# Expand_v1_01.net
KiCad netlist of a schematic drawn in EAGLE
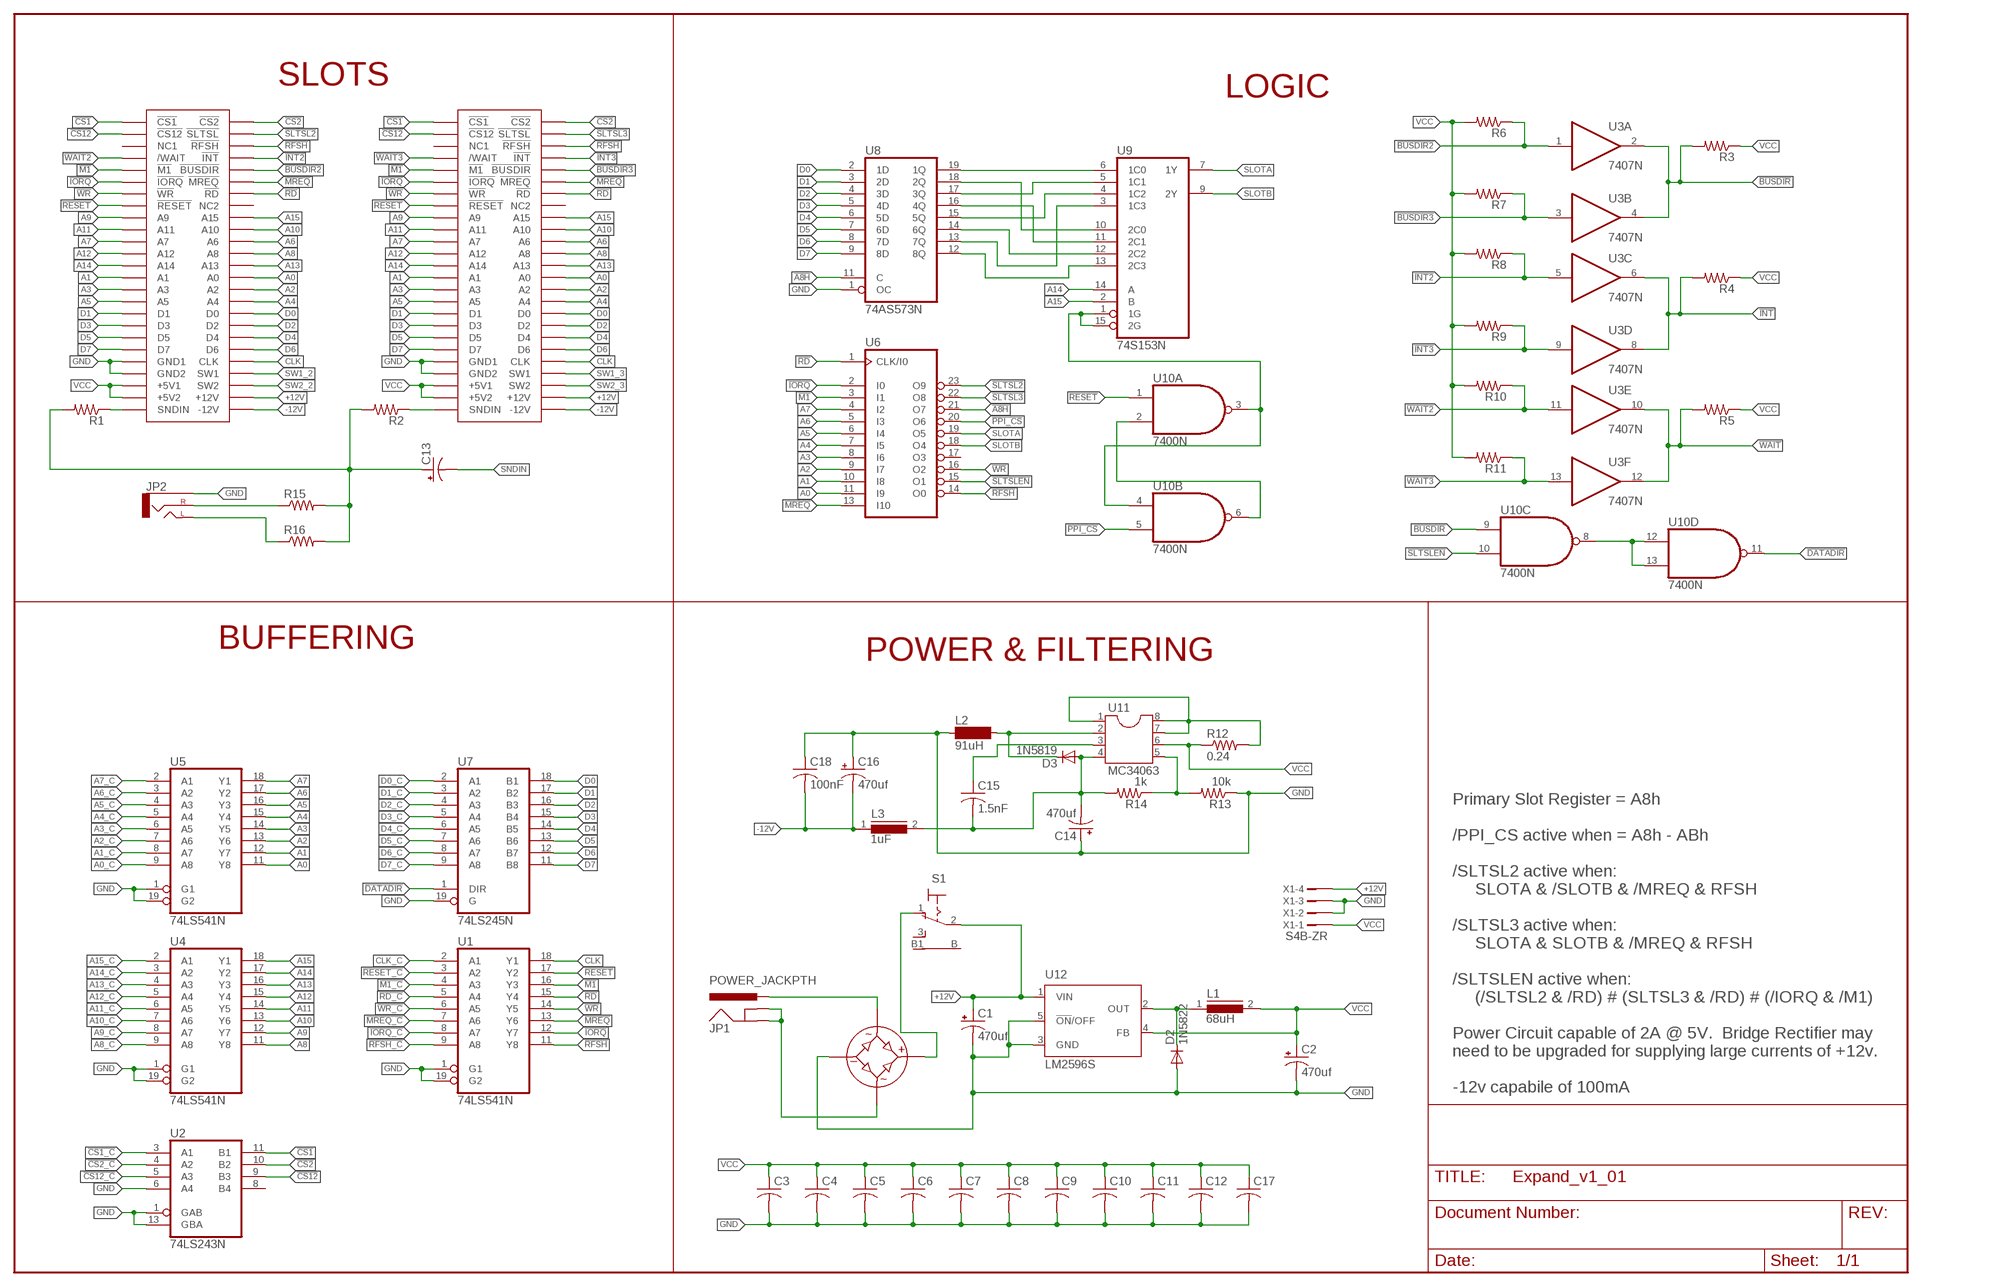
[diagram p0: schematic, sheet 1]

(export (version "E")
  (design (tool "Eeschema 10.0.6"))
  (components
    (comp (ref "C1")
      (value "470uf")
      (footprint "eagle-import:E5-10,5")
      (libsource (lib "eagle-import") (part "CPOL-USE5-10.5"))
    )
    (comp (ref "C2")
      (value "470uf")
      (footprint "eagle-import:E5-10,5")
      (libsource (lib "eagle-import") (part "CPOL-USE5-10.5"))
    )
    (comp (ref "C3")
      (value "C-US050-030X075")
      (footprint "eagle-import:C050-030X075")
      (libsource (lib "eagle-import") (part "C-US050-030X075"))
    )
    (comp (ref "C4")
      (value "C-US050-030X075")
      (footprint "eagle-import:C050-030X075")
      (libsource (lib "eagle-import") (part "C-US050-030X075"))
    )
    (comp (ref "C5")
      (value "C-US050-030X075")
      (footprint "eagle-import:C050-030X075")
      (libsource (lib "eagle-import") (part "C-US050-030X075"))
    )
    (comp (ref "C6")
      (value "C-US050-030X075")
      (footprint "eagle-import:C050-030X075")
      (libsource (lib "eagle-import") (part "C-US050-030X075"))
    )
    (comp (ref "C7")
      (value "C-US050-030X075")
      (footprint "eagle-import:C050-030X075")
      (libsource (lib "eagle-import") (part "C-US050-030X075"))
    )
    (comp (ref "C8")
      (value "C-US050-030X075")
      (footprint "eagle-import:C050-030X075")
      (libsource (lib "eagle-import") (part "C-US050-030X075"))
    )
    (comp (ref "C9")
      (value "C-US050-030X075")
      (footprint "eagle-import:C050-030X075")
      (libsource (lib "eagle-import") (part "C-US050-030X075"))
    )
    (comp (ref "C10")
      (value "C-US050-030X075")
      (footprint "eagle-import:C050-030X075")
      (libsource (lib "eagle-import") (part "C-US050-030X075"))
    )
    (comp (ref "C11")
      (value "C-US050-030X075")
      (footprint "eagle-import:C050-030X075")
      (libsource (lib "eagle-import") (part "C-US050-030X075"))
    )
    (comp (ref "C12")
      (value "C-US050-030X075")
      (footprint "eagle-import:C050-030X075")
      (libsource (lib "eagle-import") (part "C-US050-030X075"))
    )
    (comp (ref "C13")
      (value "CPOL-USE2-4")
      (footprint "eagle-import:E2-4")
      (libsource (lib "eagle-import") (part "CPOL-USE2-4"))
    )
    (comp (ref "C14")
      (value "470uf")
      (footprint "eagle-import:E5-10,5")
      (libsource (lib "eagle-import") (part "CPOL-USE5-10.5"))
    )
    (comp (ref "C15")
      (value "1.5nF")
      (footprint "eagle-import:C050-030X075")
      (libsource (lib "eagle-import") (part "C-US050-030X075"))
    )
    (comp (ref "C16")
      (value "470uf")
      (footprint "eagle-import:E5-10,5")
      (libsource (lib "eagle-import") (part "CPOL-USE5-10.5"))
    )
    (comp (ref "C17")
      (value "C-US050-030X075")
      (footprint "eagle-import:C050-030X075")
      (libsource (lib "eagle-import") (part "C-US050-030X075"))
    )
    (comp (ref "C18")
      (value "100nF")
      (footprint "eagle-import:C050-030X075")
      (libsource (lib "eagle-import") (part "C-US050-030X075"))
    )
    (comp (ref "D1")
      (value "2W10")
      (footprint "eagle-import:2W10")
      (libsource (lib "eagle-import") (part "2W10"))
    )
    (comp (ref "D2")
      (value "1N5822")
      (footprint "eagle-import:DO201-15")
      (libsource (lib "eagle-import") (part "1N5624"))
    )
    (comp (ref "D3")
      (value "1N5819")
      (footprint "eagle-import:DO15-12")
      (libsource (lib "eagle-import") (part "DIODE-DO15-12"))
    )
    (comp (ref "JP1")
      (value "POWER_JACKPTH")
      (footprint "eagle-import:POWER_JACK_PTH")
      (libsource (lib "eagle-import") (part "POWER_JACKPTH"))
    )
    (comp (ref "JP2")
      (value "AUDIO-JACK1:1")
      (footprint "eagle-import:STEREOJACK2.5MM")
      (libsource (lib "eagle-import") (part "AUDIO-JACK1{colon}1"))
    )
    (comp (ref "L1")
      (value "68uH")
      (footprint "eagle-import:A26GFC")
      (libsource (lib "eagle-import") (part "A26GFC"))
    )
    (comp (ref "L2")
      (value "91uH")
      (footprint "eagle-import:BS11")
      (libsource (lib "eagle-import") (part "BS11"))
    )
    (comp (ref "L3")
      (value "1uF")
      (footprint "eagle-import:MCC10")
      (libsource (lib "eagle-import") (part "MCC10"))
    )
    (comp (ref "R1")
      (value "R-US_0207/7")
      (footprint "eagle-import:0207_7")
      (libsource (lib "eagle-import") (part "R-US_0207/7"))
    )
    (comp (ref "R2")
      (value "R-US_0207/7")
      (footprint "eagle-import:0207_7")
      (libsource (lib "eagle-import") (part "R-US_0207/7"))
    )
    (comp (ref "R3")
      (value "R-US_0207/7")
      (footprint "eagle-import:0207_7")
      (libsource (lib "eagle-import") (part "R-US_0207/7"))
    )
    (comp (ref "R4")
      (value "R-US_0207/7")
      (footprint "eagle-import:0207_7")
      (libsource (lib "eagle-import") (part "R-US_0207/7"))
    )
    (comp (ref "R5")
      (value "R-US_0207/7")
      (footprint "eagle-import:0207_7")
      (libsource (lib "eagle-import") (part "R-US_0207/7"))
    )
    (comp (ref "R6")
      (value "R-US_0207/7")
      (footprint "eagle-import:0207_7")
      (libsource (lib "eagle-import") (part "R-US_0207/7"))
    )
    (comp (ref "R7")
      (value "R-US_0207/7")
      (footprint "eagle-import:0207_7")
      (libsource (lib "eagle-import") (part "R-US_0207/7"))
    )
    (comp (ref "R8")
      (value "R-US_0207/7")
      (footprint "eagle-import:0207_7")
      (libsource (lib "eagle-import") (part "R-US_0207/7"))
    )
    (comp (ref "R9")
      (value "R-US_0207/7")
      (footprint "eagle-import:0207_7")
      (libsource (lib "eagle-import") (part "R-US_0207/7"))
    )
    (comp (ref "R10")
      (value "R-US_0207/7")
      (footprint "eagle-import:0207_7")
      (libsource (lib "eagle-import") (part "R-US_0207/7"))
    )
    (comp (ref "R11")
      (value "R-US_0207/7")
      (footprint "eagle-import:0207_7")
      (libsource (lib "eagle-import") (part "R-US_0207/7"))
    )
    (comp (ref "R12")
      (value "0.24")
      (footprint "eagle-import:0207_7")
      (libsource (lib "eagle-import") (part "R-US_0207/7"))
    )
    (comp (ref "R13")
      (value "10k")
      (footprint "eagle-import:0207_7")
      (libsource (lib "eagle-import") (part "R-US_0207/7"))
    )
    (comp (ref "R14")
      (value "1k")
      (footprint "eagle-import:0207_7")
      (libsource (lib "eagle-import") (part "R-US_0207/7"))
    )
    (comp (ref "R15")
      (value "R-US_0207/7")
      (footprint "eagle-import:0207_7")
      (libsource (lib "eagle-import") (part "R-US_0207/7"))
    )
    (comp (ref "R16")
      (value "R-US_0207/7")
      (footprint "eagle-import:0207_7")
      (libsource (lib "eagle-import") (part "R-US_0207/7"))
    )
    (comp (ref "S1")
      (value "9070-1W")
      (footprint "eagle-import:9070-1W")
      (libsource (lib "eagle-import") (part "9070-1W"))
    )
    (comp (ref "U$1")
      (value "MSX_CART_SLOT")
      (footprint "eagle-import:CART_SLOT")
      (libsource (lib "eagle-import") (part "MSX_CART_SLOT"))
    )
    (comp (ref "U$2")
      (value "MSX_CART_SLOT")
      (footprint "eagle-import:CART_SLOT")
      (libsource (lib "eagle-import") (part "MSX_CART_SLOT"))
    )
    (comp (ref "U1")
      (value "74LS541N")
      (footprint "eagle-import:DIL20")
      (libsource (lib "eagle-import") (part "74541NLS"))
    )
    (comp (ref "U2")
      (value "74LS243N")
      (footprint "eagle-import:DIL14")
      (libsource (lib "eagle-import") (part "74243NLS"))
    )
    (comp (ref "U3")
      (value "7407N")
      (footprint "eagle-import:DIL14")
      (libsource (lib "eagle-import") (part "7407N"))
    )
    (comp (ref "U4")
      (value "74LS541N")
      (footprint "eagle-import:DIL20")
      (libsource (lib "eagle-import") (part "74541NLS"))
    )
    (comp (ref "U5")
      (value "74LS541N")
      (footprint "eagle-import:DIL20")
      (libsource (lib "eagle-import") (part "74541NLS"))
    )
    (comp (ref "U6")
      (value "22V10")
      (footprint "eagle-import:DIL24-3")
      (fields (field (name "MPN") "GAL22V10D-7LPN"))
      (libsource (lib "eagle-import") (part "22V10"))
    )
    (comp (ref "U7")
      (value "74LS245N")
      (footprint "eagle-import:DIL20")
      (libsource (lib "eagle-import") (part "74245NLS"))
    )
    (comp (ref "U8")
      (value "74AS573N")
      (footprint "eagle-import:DIL20")
      (libsource (lib "eagle-import") (part "74573NAS"))
    )
    (comp (ref "U9")
      (value "74S153N")
      (footprint "eagle-import:DIL16")
      (libsource (lib "eagle-import") (part "74153NS"))
    )
    (comp (ref "U10")
      (value "7400N")
      (footprint "eagle-import:DIL14")
      (libsource (lib "eagle-import") (part "7400N"))
    )
    (comp (ref "U11")
      (value "MC34063")
      (footprint "eagle-import:DIL08")
      (libsource (lib "eagle-import") (part "DIL8"))
    )
    (comp (ref "U12")
      (value "LM2596S")
      (footprint "eagle-import:TO263-5")
      (fields (field (name "MF") "NATIONAL SEMICONDUCTOR") (field (name "MPN") "LM2596S-ADJ/NOPB"))
      (libsource (lib "eagle-import") (part "LM2596S"))
    )
    (comp (ref "X1")
      (value "S4B-ZR")
      (footprint "eagle-import:S4B-ZR")
      (fields (field (name "MF") "FARNELL") (field (name "MPN") "S4B-ZR(LF)(SN)"))
      (libsource (lib "eagle-import") (part "?4B-ZRS"))
    )
  )
  (nets
    (net (code "1") (name "+12V") (class "Default")
      (node (ref "C1") (pin "+") (pinfunction "+_+") (pintype "passive"))
      (node (ref "S1") (pin "2") (pinfunction "P_2") (pintype "passive"))
      (node (ref "U$1") (pin "P$48") (pinfunction "+12V_P$48") (pintype "bidirectional"))
      (node (ref "U$2") (pin "P$48") (pinfunction "+12V_P$48") (pintype "bidirectional"))
      (node (ref "U12") (pin "1") (pinfunction "VIN_1") (pintype "input"))
      (node (ref "X1") (pin "4") (pinfunction "1_4") (pintype "passive"))
    )
    (net (code "2") (name "-12V") (class "Default")
      (node (ref "C16") (pin "-") (pinfunction "-_-") (pintype "passive"))
      (node (ref "C18") (pin "2") (pinfunction "2_2") (pintype "passive"))
      (node (ref "L3") (pin "1") (pinfunction "1_1") (pintype "passive"))
      (node (ref "U$1") (pin "P$50") (pinfunction "-12V_P$50") (pintype "bidirectional"))
      (node (ref "U$2") (pin "P$50") (pinfunction "-12V_P$50") (pintype "bidirectional"))
    )
    (net (code "3") (name "/~{A8H}") (class "Default")
      (node (ref "U6") (pin "21") (pinfunction "O7_21") (pintype "bidirectional"))
      (node (ref "U8") (pin "11") (pinfunction "C_11") (pintype "input"))
    )
    (net (code "4") (name "/~{BUSDIR2}") (class "Default")
      (node (ref "R6") (pin "1") (pinfunction "1_1") (pintype "passive"))
      (node (ref "U$1") (pin "P$10") (pinfunction "~{BUSDIR}_P$10") (pintype "bidirectional"))
      (node (ref "U3") (pin "1") (pinfunction "I_1") (pintype "input"))
    )
    (net (code "5") (name "/~{BUSDIR3}") (class "Default")
      (node (ref "R7") (pin "1") (pinfunction "1_1") (pintype "passive"))
      (node (ref "U$2") (pin "P$10") (pinfunction "~{BUSDIR}_P$10") (pintype "bidirectional"))
      (node (ref "U3") (pin "3") (pinfunction "I_3") (pintype "input"))
    )
    (net (code "6") (name "/~{BUSDIR}") (class "Default")
      (node (ref "R3") (pin "2") (pinfunction "2_2") (pintype "passive"))
      (node (ref "U10") (pin "9") (pinfunction "I0_9") (pintype "input"))
      (node (ref "U3") (pin "2") (pinfunction "O_2") (pintype "open_collector"))
      (node (ref "U3") (pin "4") (pinfunction "O_4") (pintype "open_collector"))
    )
    (net (code "7") (name "/~{CS1_C}") (class "Default")
      (node (ref "U2") (pin "3") (pinfunction "A1_3") (pintype "bidirectional"))
    )
    (net (code "8") (name "/~{CS1}") (class "Default")
      (node (ref "U$1") (pin "P$1") (pinfunction "~{CS1}_P$1") (pintype "bidirectional"))
      (node (ref "U$2") (pin "P$1") (pinfunction "~{CS1}_P$1") (pintype "bidirectional"))
      (node (ref "U2") (pin "11") (pinfunction "B1_11") (pintype "bidirectional"))
    )
    (net (code "9") (name "/~{CS2_C}") (class "Default")
      (node (ref "U2") (pin "4") (pinfunction "A2_4") (pintype "bidirectional"))
    )
    (net (code "10") (name "/~{CS2}") (class "Default")
      (node (ref "U$1") (pin "P$2") (pinfunction "~{CS2}_P$2") (pintype "bidirectional"))
      (node (ref "U$2") (pin "P$2") (pinfunction "~{CS2}_P$2") (pintype "bidirectional"))
      (node (ref "U2") (pin "10") (pinfunction "B2_10") (pintype "bidirectional"))
    )
    (net (code "11") (name "/~{CS12_C}") (class "Default")
      (node (ref "U2") (pin "5") (pinfunction "A3_5") (pintype "bidirectional"))
    )
    (net (code "12") (name "/~{CS12}") (class "Default")
      (node (ref "U$1") (pin "P$3") (pinfunction "~{CS12}_P$3") (pintype "bidirectional"))
      (node (ref "U$2") (pin "P$3") (pinfunction "~{CS12}_P$3") (pintype "bidirectional"))
      (node (ref "U2") (pin "9") (pinfunction "B3_9") (pintype "bidirectional"))
    )
    (net (code "13") (name "/~{DATADIR}") (class "Default")
      (node (ref "U10") (pin "11") (pinfunction "O_11") (pintype "output"))
      (node (ref "U7") (pin "1") (pinfunction "DIR_1") (pintype "input"))
    )
    (net (code "14") (name "/~{INT2}") (class "Default")
      (node (ref "R8") (pin "1") (pinfunction "1_1") (pintype "passive"))
      (node (ref "U$1") (pin "P$8") (pinfunction "~{INT}_P$8") (pintype "bidirectional"))
      (node (ref "U3") (pin "5") (pinfunction "I_5") (pintype "input"))
    )
    (net (code "15") (name "/~{INT3}") (class "Default")
      (node (ref "R9") (pin "1") (pinfunction "1_1") (pintype "passive"))
      (node (ref "U$2") (pin "P$8") (pinfunction "~{INT}_P$8") (pintype "bidirectional"))
      (node (ref "U3") (pin "9") (pinfunction "I_9") (pintype "input"))
    )
    (net (code "16") (name "/~{INT}") (class "Default")
      (node (ref "R4") (pin "2") (pinfunction "2_2") (pintype "passive"))
      (node (ref "U3") (pin "6") (pinfunction "O_6") (pintype "open_collector"))
      (node (ref "U3") (pin "8") (pinfunction "O_8") (pintype "open_collector"))
    )
    (net (code "17") (name "/~{IORQ_C}") (class "Default")
      (node (ref "U1") (pin "8") (pinfunction "A7_8") (pintype "input"))
    )
    (net (code "18") (name "/~{IORQ}") (class "Default")
      (node (ref "U$1") (pin "P$11") (pinfunction "~{IORQ}_P$11") (pintype "bidirectional"))
      (node (ref "U$2") (pin "P$11") (pinfunction "~{IORQ}_P$11") (pintype "bidirectional"))
      (node (ref "U1") (pin "12") (pinfunction "Y7_12") (pintype "tri_state"))
      (node (ref "U6") (pin "2") (pinfunction "I0_2") (pintype "input"))
    )
    (net (code "19") (name "/~{M1_C}") (class "Default")
      (node (ref "U1") (pin "4") (pinfunction "A3_4") (pintype "input"))
    )
    (net (code "20") (name "/~{M1}") (class "Default")
      (node (ref "U$1") (pin "P$9") (pinfunction "~{M1}_P$9") (pintype "bidirectional"))
      (node (ref "U$2") (pin "P$9") (pinfunction "~{M1}_P$9") (pintype "bidirectional"))
      (node (ref "U1") (pin "16") (pinfunction "Y3_16") (pintype "tri_state"))
      (node (ref "U6") (pin "3") (pinfunction "I1_3") (pintype "input"))
    )
    (net (code "21") (name "/~{MREQ_C}") (class "Default")
      (node (ref "U1") (pin "7") (pinfunction "A6_7") (pintype "input"))
    )
    (net (code "22") (name "/~{MREQ}") (class "Default")
      (node (ref "U$1") (pin "P$12") (pinfunction "~{MREQ}_P$12") (pintype "bidirectional"))
      (node (ref "U$2") (pin "P$12") (pinfunction "~{MREQ}_P$12") (pintype "bidirectional"))
      (node (ref "U1") (pin "13") (pinfunction "Y6_13") (pintype "tri_state"))
      (node (ref "U6") (pin "13") (pinfunction "I10_13") (pintype "input"))
    )
    (net (code "23") (name "/~{PPI_CS}") (class "Default")
      (node (ref "U10") (pin "5") (pinfunction "I1_5") (pintype "input"))
      (node (ref "U6") (pin "20") (pinfunction "O6_20") (pintype "bidirectional"))
    )
    (net (code "24") (name "/~{RD_C}") (class "Default")
      (node (ref "U1") (pin "5") (pinfunction "A4_5") (pintype "input"))
    )
    (net (code "25") (name "/~{RD}") (class "Default")
      (node (ref "U$1") (pin "P$14") (pinfunction "~{RD}_P$14") (pintype "bidirectional"))
      (node (ref "U$2") (pin "P$14") (pinfunction "~{RD}_P$14") (pintype "bidirectional"))
      (node (ref "U1") (pin "15") (pinfunction "Y4_15") (pintype "tri_state"))
      (node (ref "U6") (pin "1") (pinfunction "CLK/I0_1") (pintype "input"))
    )
    (net (code "26") (name "/~{RESET_C}") (class "Default")
      (node (ref "U1") (pin "3") (pinfunction "A2_3") (pintype "input"))
    )
    (net (code "27") (name "/~{RESET}") (class "Default")
      (node (ref "U$1") (pin "P$15") (pinfunction "~{RESET}_P$15") (pintype "bidirectional"))
      (node (ref "U$2") (pin "P$15") (pinfunction "~{RESET}_P$15") (pintype "bidirectional"))
      (node (ref "U1") (pin "17") (pinfunction "Y2_17") (pintype "tri_state"))
      (node (ref "U10") (pin "1") (pinfunction "I0_1") (pintype "input"))
    )
    (net (code "28") (name "/~{RFSH_C}") (class "Default")
      (node (ref "U1") (pin "9") (pinfunction "A8_9") (pintype "input"))
    )
    (net (code "29") (name "/~{RFSH}") (class "Default")
      (node (ref "U$1") (pin "P$6") (pinfunction "~{RFSH}_P$6") (pintype "bidirectional"))
      (node (ref "U$2") (pin "P$6") (pinfunction "~{RFSH}_P$6") (pintype "bidirectional"))
      (node (ref "U1") (pin "11") (pinfunction "Y8_11") (pintype "tri_state"))
      (node (ref "U6") (pin "14") (pinfunction "O0_14") (pintype "bidirectional"))
    )
    (net (code "30") (name "/~{SLTSL2}") (class "Default")
      (node (ref "U$1") (pin "P$4") (pinfunction "~{SLTSL}_P$4") (pintype "bidirectional"))
      (node (ref "U6") (pin "23") (pinfunction "O9_23") (pintype "bidirectional"))
    )
    (net (code "31") (name "/~{SLTSL3}") (class "Default")
      (node (ref "U$2") (pin "P$4") (pinfunction "~{SLTSL}_P$4") (pintype "bidirectional"))
      (node (ref "U6") (pin "22") (pinfunction "O8_22") (pintype "bidirectional"))
    )
    (net (code "32") (name "/~{SLTSLEN}") (class "Default")
      (node (ref "U10") (pin "10") (pinfunction "I1_10") (pintype "input"))
      (node (ref "U6") (pin "15") (pinfunction "O1_15") (pintype "bidirectional"))
    )
    (net (code "33") (name "/~{WAIT2}") (class "Default")
      (node (ref "R10") (pin "1") (pinfunction "1_1") (pintype "passive"))
      (node (ref "U$1") (pin "P$7") (pinfunction "/WAIT_P$7") (pintype "bidirectional"))
      (node (ref "U3") (pin "11") (pinfunction "I_11") (pintype "input"))
    )
    (net (code "34") (name "/~{WAIT3}") (class "Default")
      (node (ref "R11") (pin "1") (pinfunction "1_1") (pintype "passive"))
      (node (ref "U$2") (pin "P$7") (pinfunction "/WAIT_P$7") (pintype "bidirectional"))
      (node (ref "U3") (pin "13") (pinfunction "I_13") (pintype "input"))
    )
    (net (code "35") (name "/~{WAIT}") (class "Default")
      (node (ref "R5") (pin "2") (pinfunction "2_2") (pintype "passive"))
      (node (ref "U3") (pin "10") (pinfunction "O_10") (pintype "open_collector"))
      (node (ref "U3") (pin "12") (pinfunction "O_12") (pintype "open_collector"))
    )
    (net (code "36") (name "/~{WR_C}") (class "Default")
      (node (ref "U1") (pin "6") (pinfunction "A5_6") (pintype "input"))
    )
    (net (code "37") (name "/~{WR}") (class "Default")
      (node (ref "U$1") (pin "P$13") (pinfunction "~{WR}_P$13") (pintype "bidirectional"))
      (node (ref "U$2") (pin "P$13") (pinfunction "~{WR}_P$13") (pintype "bidirectional"))
      (node (ref "U1") (pin "14") (pinfunction "Y5_14") (pintype "tri_state"))
      (node (ref "U6") (pin "16") (pinfunction "O2_16") (pintype "bidirectional"))
    )
    (net (code "38") (name "A0") (class "Default")
      (node (ref "U$1") (pin "P$28") (pinfunction "A0_P$28") (pintype "bidirectional"))
      (node (ref "U$2") (pin "P$28") (pinfunction "A0_P$28") (pintype "bidirectional"))
      (node (ref "U5") (pin "11") (pinfunction "Y8_11") (pintype "tri_state"))
      (node (ref "U6") (pin "11") (pinfunction "I9_11") (pintype "input"))
    )
    (net (code "39") (name "A0_C") (class "Default")
      (node (ref "U5") (pin "9") (pinfunction "A8_9") (pintype "input"))
    )
    (net (code "40") (name "A1") (class "Default")
      (node (ref "U$1") (pin "P$27") (pinfunction "A1_P$27") (pintype "bidirectional"))
      (node (ref "U$2") (pin "P$27") (pinfunction "A1_P$27") (pintype "bidirectional"))
      (node (ref "U5") (pin "12") (pinfunction "Y7_12") (pintype "tri_state"))
      (node (ref "U6") (pin "10") (pinfunction "I8_10") (pintype "input"))
    )
    (net (code "41") (name "A1_C") (class "Default")
      (node (ref "U5") (pin "8") (pinfunction "A7_8") (pintype "input"))
    )
    (net (code "42") (name "A2") (class "Default")
      (node (ref "U$1") (pin "P$30") (pinfunction "A2_P$30") (pintype "bidirectional"))
      (node (ref "U$2") (pin "P$30") (pinfunction "A2_P$30") (pintype "bidirectional"))
      (node (ref "U5") (pin "13") (pinfunction "Y6_13") (pintype "tri_state"))
      (node (ref "U6") (pin "9") (pinfunction "I7_9") (pintype "input"))
    )
    (net (code "43") (name "A2_C") (class "Default")
      (node (ref "U5") (pin "7") (pinfunction "A6_7") (pintype "input"))
    )
    (net (code "44") (name "A3") (class "Default")
      (node (ref "U$1") (pin "P$29") (pinfunction "A3_P$29") (pintype "bidirectional"))
      (node (ref "U$2") (pin "P$29") (pinfunction "A3_P$29") (pintype "bidirectional"))
      (node (ref "U5") (pin "14") (pinfunction "Y5_14") (pintype "tri_state"))
      (node (ref "U6") (pin "8") (pinfunction "I6_8") (pintype "input"))
    )
    (net (code "45") (name "A3_C") (class "Default")
      (node (ref "U5") (pin "6") (pinfunction "A5_6") (pintype "input"))
    )
    (net (code "46") (name "A4") (class "Default")
      (node (ref "U$1") (pin "P$32") (pinfunction "A4_P$32") (pintype "bidirectional"))
      (node (ref "U$2") (pin "P$32") (pinfunction "A4_P$32") (pintype "bidirectional"))
      (node (ref "U5") (pin "15") (pinfunction "Y4_15") (pintype "tri_state"))
      (node (ref "U6") (pin "7") (pinfunction "I5_7") (pintype "input"))
    )
    (net (code "47") (name "A4_C") (class "Default")
      (node (ref "U5") (pin "5") (pinfunction "A4_5") (pintype "input"))
    )
    (net (code "48") (name "A5") (class "Default")
      (node (ref "U$1") (pin "P$31") (pinfunction "A5_P$31") (pintype "bidirectional"))
      (node (ref "U$2") (pin "P$31") (pinfunction "A5_P$31") (pintype "bidirectional"))
      (node (ref "U5") (pin "16") (pinfunction "Y3_16") (pintype "tri_state"))
      (node (ref "U6") (pin "6") (pinfunction "I4_6") (pintype "input"))
    )
    (net (code "49") (name "A5_C") (class "Default")
      (node (ref "U5") (pin "4") (pinfunction "A3_4") (pintype "input"))
    )
    (net (code "50") (name "A6") (class "Default")
      (node (ref "U$1") (pin "P$22") (pinfunction "A6_P$22") (pintype "bidirectional"))
      (node (ref "U$2") (pin "P$22") (pinfunction "A6_P$22") (pintype "bidirectional"))
      (node (ref "U5") (pin "17") (pinfunction "Y2_17") (pintype "tri_state"))
      (node (ref "U6") (pin "5") (pinfunction "I3_5") (pintype "input"))
    )
    (net (code "51") (name "A6_C") (class "Default")
      (node (ref "U5") (pin "3") (pinfunction "A2_3") (pintype "input"))
    )
    (net (code "52") (name "A7") (class "Default")
      (node (ref "U$1") (pin "P$21") (pinfunction "A7_P$21") (pintype "bidirectional"))
      (node (ref "U$2") (pin "P$21") (pinfunction "A7_P$21") (pintype "bidirectional"))
      (node (ref "U5") (pin "18") (pinfunction "Y1_18") (pintype "tri_state"))
      (node (ref "U6") (pin "4") (pinfunction "I2_4") (pintype "input"))
    )
    (net (code "53") (name "A7_C") (class "Default")
      (node (ref "U5") (pin "2") (pinfunction "A1_2") (pintype "input"))
    )
    (net (code "54") (name "A8") (class "Default")
      (node (ref "U$1") (pin "P$24") (pinfunction "A8_P$24") (pintype "bidirectional"))
      (node (ref "U$2") (pin "P$24") (pinfunction "A8_P$24") (pintype "bidirectional"))
      (node (ref "U4") (pin "11") (pinfunction "Y8_11") (pintype "tri_state"))
    )
    (net (code "55") (name "A8_C") (class "Default")
      (node (ref "U4") (pin "9") (pinfunction "A8_9") (pintype "input"))
    )
    (net (code "56") (name "A9") (class "Default")
      (node (ref "U$1") (pin "P$17") (pinfunction "A9_P$17") (pintype "bidirectional"))
      (node (ref "U$2") (pin "P$17") (pinfunction "A9_P$17") (pintype "bidirectional"))
      (node (ref "U4") (pin "12") (pinfunction "Y7_12") (pintype "tri_state"))
    )
    (net (code "57") (name "A9_C") (class "Default")
      (node (ref "U4") (pin "8") (pinfunction "A7_8") (pintype "input"))
    )
    (net (code "58") (name "A10") (class "Default")
      (node (ref "U$1") (pin "P$20") (pinfunction "A10_P$20") (pintype "bidirectional"))
      (node (ref "U$2") (pin "P$20") (pinfunction "A10_P$20") (pintype "bidirectional"))
      (node (ref "U4") (pin "13") (pinfunction "Y6_13") (pintype "tri_state"))
    )
    (net (code "59") (name "A10_C") (class "Default")
      (node (ref "U4") (pin "7") (pinfunction "A6_7") (pintype "input"))
    )
    (net (code "60") (name "A11") (class "Default")
      (node (ref "U$1") (pin "P$19") (pinfunction "A11_P$19") (pintype "bidirectional"))
      (node (ref "U$2") (pin "P$19") (pinfunction "A11_P$19") (pintype "bidirectional"))
      (node (ref "U4") (pin "14") (pinfunction "Y5_14") (pintype "tri_state"))
    )
    (net (code "61") (name "A11_C") (class "Default")
      (node (ref "U4") (pin "6") (pinfunction "A5_6") (pintype "input"))
    )
    (net (code "62") (name "A12") (class "Default")
      (node (ref "U$1") (pin "P$23") (pinfunction "A12_P$23") (pintype "bidirectional"))
      (node (ref "U$2") (pin "P$23") (pinfunction "A12_P$23") (pintype "bidirectional"))
      (node (ref "U4") (pin "15") (pinfunction "Y4_15") (pintype "tri_state"))
    )
    (net (code "63") (name "A12_C") (class "Default")
      (node (ref "U4") (pin "5") (pinfunction "A4_5") (pintype "input"))
    )
    (net (code "64") (name "A13") (class "Default")
      (node (ref "U$1") (pin "P$26") (pinfunction "A13_P$26") (pintype "bidirectional"))
      (node (ref "U$2") (pin "P$26") (pinfunction "A13_P$26") (pintype "bidirectional"))
      (node (ref "U4") (pin "16") (pinfunction "Y3_16") (pintype "tri_state"))
    )
    (net (code "65") (name "A13_C") (class "Default")
      (node (ref "U4") (pin "4") (pinfunction "A3_4") (pintype "input"))
    )
    (net (code "66") (name "A14") (class "Default")
      (node (ref "U$1") (pin "P$25") (pinfunction "A14_P$25") (pintype "bidirectional"))
      (node (ref "U$2") (pin "P$25") (pinfunction "A14_P$25") (pintype "bidirectional"))
      (node (ref "U4") (pin "17") (pinfunction "Y2_17") (pintype "tri_state"))
      (node (ref "U9") (pin "14") (pinfunction "A_14") (pintype "input"))
    )
    (net (code "67") (name "A14_C") (class "Default")
      (node (ref "U4") (pin "3") (pinfunction "A2_3") (pintype "input"))
    )
    (net (code "68") (name "A15") (class "Default")
      (node (ref "U$1") (pin "P$18") (pinfunction "A15_P$18") (pintype "bidirectional"))
      (node (ref "U$2") (pin "P$18") (pinfunction "A15_P$18") (pintype "bidirectional"))
      (node (ref "U4") (pin "18") (pinfunction "Y1_18") (pintype "tri_state"))
      (node (ref "U9") (pin "2") (pinfunction "B_2") (pintype "input"))
    )
    (net (code "69") (name "A15_C") (class "Default")
      (node (ref "U4") (pin "2") (pinfunction "A1_2") (pintype "input"))
    )
    (net (code "70") (name "CLK") (class "Default")
      (node (ref "U$1") (pin "P$42") (pinfunction "CLK_P$42") (pintype "bidirectional"))
      (node (ref "U$2") (pin "P$42") (pinfunction "CLK_P$42") (pintype "bidirectional"))
      (node (ref "U1") (pin "18") (pinfunction "Y1_18") (pintype "tri_state"))
    )
    (net (code "71") (name "CLK_C") (class "Default")
      (node (ref "U1") (pin "2") (pinfunction "A1_2") (pintype "input"))
    )
    (net (code "72") (name "D0") (class "Default")
      (node (ref "U$1") (pin "P$34") (pinfunction "D0_P$34") (pintype "bidirectional"))
      (node (ref "U$2") (pin "P$34") (pinfunction "D0_P$34") (pintype "bidirectional"))
      (node (ref "U7") (pin "18") (pinfunction "B1_18") (pintype "bidirectional"))
      (node (ref "U8") (pin "2") (pinfunction "1D_2") (pintype "input"))
    )
    (net (code "73") (name "D0_C") (class "Default")
      (node (ref "U7") (pin "2") (pinfunction "A1_2") (pintype "bidirectional"))
    )
    (net (code "74") (name "D1") (class "Default")
      (node (ref "U$1") (pin "P$33") (pinfunction "D1_P$33") (pintype "bidirectional"))
      (node (ref "U$2") (pin "P$33") (pinfunction "D1_P$33") (pintype "bidirectional"))
      (node (ref "U7") (pin "17") (pinfunction "B2_17") (pintype "bidirectional"))
      (node (ref "U8") (pin "3") (pinfunction "2D_3") (pintype "input"))
    )
    (net (code "75") (name "D1_C") (class "Default")
      (node (ref "U7") (pin "3") (pinfunction "A2_3") (pintype "bidirectional"))
    )
    (net (code "76") (name "D2") (class "Default")
      (node (ref "U$1") (pin "P$36") (pinfunction "D2_P$36") (pintype "bidirectional"))
      (node (ref "U$2") (pin "P$36") (pinfunction "D2_P$36") (pintype "bidirectional"))
      (node (ref "U7") (pin "16") (pinfunction "B3_16") (pintype "bidirectional"))
      (node (ref "U8") (pin "4") (pinfunction "3D_4") (pintype "input"))
    )
    (net (code "77") (name "D2_C") (class "Default")
      (node (ref "U7") (pin "4") (pinfunction "A3_4") (pintype "bidirectional"))
    )
    (net (code "78") (name "D3") (class "Default")
      (node (ref "U$1") (pin "P$35") (pinfunction "D3_P$35") (pintype "bidirectional"))
      (node (ref "U$2") (pin "P$35") (pinfunction "D3_P$35") (pintype "bidirectional"))
      (node (ref "U7") (pin "15") (pinfunction "B4_15") (pintype "bidirectional"))
      (node (ref "U8") (pin "5") (pinfunction "4D_5") (pintype "input"))
    )
    (net (code "79") (name "D3_C") (class "Default")
      (node (ref "U7") (pin "5") (pinfunction "A4_5") (pintype "bidirectional"))
    )
    (net (code "80") (name "D4") (class "Default")
      (node (ref "U$1") (pin "P$38") (pinfunction "D4_P$38") (pintype "bidirectional"))
      (node (ref "U$2") (pin "P$38") (pinfunction "D4_P$38") (pintype "bidirectional"))
      (node (ref "U7") (pin "14") (pinfunction "B5_14") (pintype "bidirectional"))
      (node (ref "U8") (pin "6") (pinfunction "5D_6") (pintype "input"))
    )
    (net (code "81") (name "D4_C") (class "Default")
      (node (ref "U7") (pin "6") (pinfunction "A5_6") (pintype "bidirectional"))
    )
    (net (code "82") (name "D5") (class "Default")
      (node (ref "U$1") (pin "P$37") (pinfunction "D5_P$37") (pintype "bidirectional"))
      (node (ref "U$2") (pin "P$37") (pinfunction "D5_P$37") (pintype "bidirectional"))
      (node (ref "U7") (pin "13") (pinfunction "B6_13") (pintype "bidirectional"))
      (node (ref "U8") (pin "7") (pinfunction "6D_7") (pintype "input"))
    )
    (net (code "83") (name "D5_C") (class "Default")
      (node (ref "U7") (pin "7") (pinfunction "A6_7") (pintype "bidirectional"))
    )
    (net (code "84") (name "D6") (class "Default")
      (node (ref "U$1") (pin "P$40") (pinfunction "D6_P$40") (pintype "bidirectional"))
      (node (ref "U$2") (pin "P$40") (pinfunction "D6_P$40") (pintype "bidirectional"))
      (node (ref "U7") (pin "12") (pinfunction "B7_12") (pintype "bidirectional"))
      (node (ref "U8") (pin "8") (pinfunction "7D_8") (pintype "input"))
    )
    (net (code "85") (name "D6_C") (class "Default")
      (node (ref "U7") (pin "8") (pinfunction "A7_8") (pintype "bidirectional"))
    )
    (net (code "86") (name "D7") (class "Default")
      (node (ref "U$1") (pin "P$39") (pinfunction "D7_P$39") (pintype "bidirectional"))
      (node (ref "U$2") (pin "P$39") (pinfunction "D7_P$39") (pintype "bidirectional"))
      (node (ref "U7") (pin "11") (pinfunction "B8_11") (pintype "bidirectional"))
      (node (ref "U8") (pin "9") (pinfunction "8D_9") (pintype "input"))
    )
    (net (code "87") (name "D7_C") (class "Default")
      (node (ref "U7") (pin "9") (pinfunction "A8_9") (pintype "bidirectional"))
    )
    (net (code "88") (name "GND") (class "Default")
      (node (ref "C1") (pin "-") (pinfunction "-_-") (pintype "passive"))
      (node (ref "C10") (pin "2") (pinfunction "2_2") (pintype "passive"))
      (node (ref "C11") (pin "2") (pinfunction "2_2") (pintype "passive"))
      (node (ref "C12") (pin "2") (pinfunction "2_2") (pintype "passive"))
      (node (ref "C14") (pin "+") (pinfunction "+_+") (pintype "passive"))
      (node (ref "C16") (pin "+") (pinfunction "+_+") (pintype "passive"))
      (node (ref "C17") (pin "2") (pinfunction "2_2") (pintype "passive"))
      (node (ref "C18") (pin "1") (pinfunction "1_1") (pintype "passive"))
      (node (ref "C2") (pin "-") (pinfunction "-_-") (pintype "passive"))
      (node (ref "C3") (pin "2") (pinfunction "2_2") (pintype "passive"))
      (node (ref "C4") (pin "2") (pinfunction "2_2") (pintype "passive"))
      (node (ref "C5") (pin "2") (pinfunction "2_2") (pintype "passive"))
      (node (ref "C6") (pin "2") (pinfunction "2_2") (pintype "passive"))
      (node (ref "C7") (pin "2") (pinfunction "2_2") (pintype "passive"))
      (node (ref "C8") (pin "2") (pinfunction "2_2") (pintype "passive"))
      (node (ref "C9") (pin "2") (pinfunction "2_2") (pintype "passive"))
      (node (ref "D1") (pin "P$4") (pinfunction "P$4_P$4") (pintype "bidirectional"))
      (node (ref "D2") (pin "A") (pinfunction "A_A") (pintype "passive"))
      (node (ref "JP2") (pin "5") (pinfunction "SLEEVE_5") (pintype "bidirectional"))
      (node (ref "L2") (pin "1") (pinfunction "1_1") (pintype "passive"))
      (node (ref "R13") (pin "1") (pinfunction "1_1") (pintype "passive"))
      (node (ref "U$1") (pin "P$41") (pinfunction "GND1_P$41") (pintype "bidirectional"))
      (node (ref "U$1") (pin "P$43") (pinfunction "GND2_P$43") (pintype "bidirectional"))
      (node (ref "U$2") (pin "P$41") (pinfunction "GND1_P$41") (pintype "bidirectional"))
      (node (ref "U$2") (pin "P$43") (pinfunction "GND2_P$43") (pintype "bidirectional"))
      (node (ref "U1") (pin "1") (pinfunction "G1_1") (pintype "input"))
      (node (ref "U1") (pin "19") (pinfunction "G2_19") (pintype "input"))
      (node (ref "U12") (pin "3") (pinfunction "GND_3") (pintype "power_in"))
      (node (ref "U12") (pin "5") (pinfunction "~{ON}/OFF_5") (pintype "input"))
      (node (ref "U2") (pin "1") (pinfunction "GAB_1") (pintype "input"))
      (node (ref "U2") (pin "13") (pinfunction "GBA_13") (pintype "input"))
      (node (ref "U2") (pin "6") (pinfunction "A4_6") (pintype "bidirectional"))
      (node (ref "U4") (pin "1") (pinfunction "G1_1") (pintype "input"))
      (node (ref "U4") (pin "19") (pinfunction "G2_19") (pintype "input"))
      (node (ref "U5") (pin "1") (pinfunction "G1_1") (pintype "input"))
      (node (ref "U5") (pin "19") (pinfunction "G2_19") (pintype "input"))
      (node (ref "U7") (pin "19") (pinfunction "G_19") (pintype "input"))
      (node (ref "U8") (pin "1") (pinfunction "OC_1") (pintype "input"))
      (node (ref "X1") (pin "2") (pinfunction "1_2") (pintype "passive"))
      (node (ref "X1") (pin "3") (pinfunction "1_3") (pintype "passive"))
    )
    (net (code "89") (name "Net-(C13-Pad+)") (class "Default")
      (node (ref "C13") (pin "+") (pinfunction "+_+") (pintype "passive"))
      (node (ref "R1") (pin "2") (pinfunction "2_2") (pintype "passive"))
      (node (ref "R15") (pin "2") (pinfunction "2_2") (pintype "passive"))
      (node (ref "R16") (pin "2") (pinfunction "2_2") (pintype "passive"))
      (node (ref "R2") (pin "2") (pinfunction "2_2") (pintype "passive"))
    )
    (net (code "90") (name "Net-(C14-Pad-)") (class "Default")
      (node (ref "C14") (pin "-") (pinfunction "-_-") (pintype "passive"))
      (node (ref "C15") (pin "2") (pinfunction "2_2") (pintype "passive"))
      (node (ref "D3") (pin "A") (pinfunction "A_A") (pintype "passive"))
      (node (ref "L3") (pin "2") (pinfunction "2_2") (pintype "passive"))
      (node (ref "R14") (pin "2") (pinfunction "2_2") (pintype "passive"))
      (node (ref "U11") (pin "4") (pinfunction "4_4") (pintype "passive"))
    )
    (net (code "91") (name "Net-(C15-Pad1)") (class "Default")
      (node (ref "C15") (pin "1") (pinfunction "1_1") (pintype "passive"))
      (node (ref "U11") (pin "3") (pinfunction "3_3") (pintype "passive"))
    )
    (net (code "92") (name "Net-(D1-PadP$1)") (class "Default")
      (node (ref "D1") (pin "P$1") (pinfunction "P$1_P$1") (pintype "bidirectional"))
      (node (ref "JP1") (pin "PWR") (pinfunction "PWR_PWR") (pintype "bidirectional"))
    )
    (net (code "93") (name "Net-(D1-PadP$3)") (class "Default")
      (node (ref "D1") (pin "P$3") (pinfunction "P$3_P$3") (pintype "bidirectional"))
      (node (ref "JP1") (pin "GND") (pinfunction "GND_GND") (pintype "bidirectional"))
      (node (ref "JP1") (pin "GNDBREAK") (pinfunction "GNDBREAK_GNDBREAK") (pintype "bidirectional"))
    )
    (net (code "94") (name "Net-(D3-PadC)") (class "Default")
      (node (ref "D3") (pin "C") (pinfunction "C_C") (pintype "passive"))
      (node (ref "L2") (pin "2") (pinfunction "2_2") (pintype "passive"))
      (node (ref "U11") (pin "2") (pinfunction "2_2") (pintype "passive"))
    )
    (net (code "95") (name "Net-(JP2-LEFT)") (class "Default")
      (node (ref "JP2") (pin "1") (pinfunction "LEFT_1") (pintype "bidirectional"))
      (node (ref "R16") (pin "1") (pinfunction "1_1") (pintype "passive"))
    )
    (net (code "96") (name "Net-(JP2-RIGHT)") (class "Default")
      (node (ref "JP2") (pin "4") (pinfunction "RIGHT_4") (pintype "bidirectional"))
      (node (ref "R15") (pin "1") (pinfunction "1_1") (pintype "passive"))
    )
    (net (code "97") (name "Net-(R12-Pad2)") (class "Default")
      (node (ref "R12") (pin "2") (pinfunction "2_2") (pintype "passive"))
      (node (ref "U11") (pin "1") (pinfunction "1_1") (pintype "passive"))
      (node (ref "U11") (pin "7") (pinfunction "7_7") (pintype "passive"))
      (node (ref "U11") (pin "8") (pinfunction "8_8") (pintype "passive"))
    )
    (net (code "98") (name "Net-(R13-Pad2)") (class "Default")
      (node (ref "R13") (pin "2") (pinfunction "2_2") (pintype "passive"))
      (node (ref "R14") (pin "1") (pinfunction "1_1") (pintype "passive"))
      (node (ref "U11") (pin "5") (pinfunction "5_5") (pintype "passive"))
    )
    (net (code "99") (name "Net-(S1-O)") (class "Default")
      (node (ref "D1") (pin "P$2") (pinfunction "P$2_P$2") (pintype "bidirectional"))
      (node (ref "S1") (pin "1") (pinfunction "O_1") (pintype "passive"))
    )
    (net (code "100") (name "Net-(U$1-SNDIN)") (class "Default")
      (node (ref "R1") (pin "1") (pinfunction "1_1") (pintype "passive"))
      (node (ref "U$1") (pin "P$49") (pinfunction "SNDIN_P$49") (pintype "bidirectional"))
    )
    (net (code "101") (name "Net-(U$2-SNDIN)") (class "Default")
      (node (ref "R2") (pin "1") (pinfunction "1_1") (pintype "passive"))
      (node (ref "U$2") (pin "P$49") (pinfunction "SNDIN_P$49") (pintype "bidirectional"))
    )
    (net (code "102") (name "Net-(U8A-1Q)") (class "Default")
      (node (ref "U8") (pin "19") (pinfunction "1Q_19") (pintype "tri_state"))
      (node (ref "U9") (pin "6") (pinfunction "1C0_6") (pintype "input"))
    )
    (net (code "103") (name "Net-(U8A-2Q)") (class "Default")
      (node (ref "U8") (pin "18") (pinfunction "2Q_18") (pintype "tri_state"))
      (node (ref "U9") (pin "10") (pinfunction "2C0_10") (pintype "input"))
    )
    (net (code "104") (name "Net-(U8A-3Q)") (class "Default")
      (node (ref "U8") (pin "17") (pinfunction "3Q_17") (pintype "tri_state"))
      (node (ref "U9") (pin "5") (pinfunction "1C1_5") (pintype "input"))
    )
    (net (code "105") (name "Net-(U8A-4Q)") (class "Default")
      (node (ref "U8") (pin "16") (pinfunction "4Q_16") (pintype "tri_state"))
      (node (ref "U9") (pin "11") (pinfunction "2C1_11") (pintype "input"))
    )
    (net (code "106") (name "Net-(U8A-5Q)") (class "Default")
      (node (ref "U8") (pin "15") (pinfunction "5Q_15") (pintype "tri_state"))
      (node (ref "U9") (pin "4") (pinfunction "1C2_4") (pintype "input"))
    )
    (net (code "107") (name "Net-(U8A-6Q)") (class "Default")
      (node (ref "U8") (pin "14") (pinfunction "6Q_14") (pintype "tri_state"))
      (node (ref "U9") (pin "12") (pinfunction "2C2_12") (pintype "input"))
    )
    (net (code "108") (name "Net-(U8A-7Q)") (class "Default")
      (node (ref "U8") (pin "13") (pinfunction "7Q_13") (pintype "tri_state"))
      (node (ref "U9") (pin "3") (pinfunction "1C3_3") (pintype "input"))
    )
    (net (code "109") (name "Net-(U8A-8Q)") (class "Default")
      (node (ref "U8") (pin "12") (pinfunction "8Q_12") (pintype "tri_state"))
      (node (ref "U9") (pin "13") (pinfunction "2C3_13") (pintype "input"))
    )
    (net (code "110") (name "Net-(U10A-I1)") (class "Default")
      (node (ref "U10") (pin "2") (pinfunction "I1_2") (pintype "input"))
      (node (ref "U10") (pin "6") (pinfunction "O_6") (pintype "output"))
    )
    (net (code "111") (name "Net-(U10A-O)") (class "Default")
      (node (ref "U10") (pin "3") (pinfunction "O_3") (pintype "output"))
      (node (ref "U10") (pin "4") (pinfunction "I0_4") (pintype "input"))
      (node (ref "U9") (pin "1") (pinfunction "1G_1") (pintype "input"))
      (node (ref "U9") (pin "15") (pinfunction "2G_15") (pintype "input"))
    )
    (net (code "112") (name "Net-(U10C-O)") (class "Default")
      (node (ref "U10") (pin "12") (pinfunction "I0_12") (pintype "input"))
      (node (ref "U10") (pin "13") (pinfunction "I1_13") (pintype "input"))
      (node (ref "U10") (pin "8") (pinfunction "O_8") (pintype "output"))
    )
    (net (code "113") (name "Net-(U12-OUT)") (class "Default")
      (node (ref "D2") (pin "C") (pinfunction "C_C") (pintype "passive"))
      (node (ref "L1") (pin "1") (pinfunction "1_1") (pintype "passive"))
      (node (ref "U12") (pin "2") (pinfunction "OUT_2") (pintype "output"))
    )
    (net (code "114") (name "SLOTA") (class "Default")
      (node (ref "U6") (pin "19") (pinfunction "O5_19") (pintype "bidirectional"))
      (node (ref "U9") (pin "7") (pinfunction "1Y_7") (pintype "output"))
    )
    (net (code "115") (name "SLOTB") (class "Default")
      (node (ref "U6") (pin "18") (pinfunction "O4_18") (pintype "bidirectional"))
      (node (ref "U9") (pin "9") (pinfunction "2Y_9") (pintype "output"))
    )
    (net (code "116") (name "SNDIN") (class "Default")
      (node (ref "C13") (pin "-") (pinfunction "-_-") (pintype "passive"))
    )
    (net (code "117") (name "SW1_2") (class "Default")
      (node (ref "U$1") (pin "P$44") (pinfunction "SW1_P$44") (pintype "bidirectional"))
    )
    (net (code "118") (name "SW1_3") (class "Default")
      (node (ref "U$2") (pin "P$44") (pinfunction "SW1_P$44") (pintype "bidirectional"))
    )
    (net (code "119") (name "SW2_2") (class "Default")
      (node (ref "U$1") (pin "P$46") (pinfunction "SW2_P$46") (pintype "bidirectional"))
    )
    (net (code "120") (name "SW2_3") (class "Default")
      (node (ref "U$2") (pin "P$46") (pinfunction "SW2_P$46") (pintype "bidirectional"))
    )
    (net (code "121") (name "VCC") (class "Default")
      (node (ref "C10") (pin "1") (pinfunction "1_1") (pintype "passive"))
      (node (ref "C11") (pin "1") (pinfunction "1_1") (pintype "passive"))
      (node (ref "C12") (pin "1") (pinfunction "1_1") (pintype "passive"))
      (node (ref "C17") (pin "1") (pinfunction "1_1") (pintype "passive"))
      (node (ref "C2") (pin "+") (pinfunction "+_+") (pintype "passive"))
      (node (ref "C3") (pin "1") (pinfunction "1_1") (pintype "passive"))
      (node (ref "C4") (pin "1") (pinfunction "1_1") (pintype "passive"))
      (node (ref "C5") (pin "1") (pinfunction "1_1") (pintype "passive"))
      (node (ref "C6") (pin "1") (pinfunction "1_1") (pintype "passive"))
      (node (ref "C7") (pin "1") (pinfunction "1_1") (pintype "passive"))
      (node (ref "C8") (pin "1") (pinfunction "1_1") (pintype "passive"))
      (node (ref "C9") (pin "1") (pinfunction "1_1") (pintype "passive"))
      (node (ref "L1") (pin "2") (pinfunction "2_2") (pintype "passive"))
      (node (ref "R10") (pin "2") (pinfunction "2_2") (pintype "passive"))
      (node (ref "R11") (pin "2") (pinfunction "2_2") (pintype "passive"))
      (node (ref "R12") (pin "1") (pinfunction "1_1") (pintype "passive"))
      (node (ref "R3") (pin "1") (pinfunction "1_1") (pintype "passive"))
      (node (ref "R4") (pin "1") (pinfunction "1_1") (pintype "passive"))
      (node (ref "R5") (pin "1") (pinfunction "1_1") (pintype "passive"))
      (node (ref "R6") (pin "2") (pinfunction "2_2") (pintype "passive"))
      (node (ref "R7") (pin "2") (pinfunction "2_2") (pintype "passive"))
      (node (ref "R8") (pin "2") (pinfunction "2_2") (pintype "passive"))
      (node (ref "R9") (pin "2") (pinfunction "2_2") (pintype "passive"))
      (node (ref "U$1") (pin "P$45") (pinfunction "+5V1_P$45") (pintype "bidirectional"))
      (node (ref "U$1") (pin "P$47") (pinfunction "+5V2_P$47") (pintype "bidirectional"))
      (node (ref "U$2") (pin "P$45") (pinfunction "+5V1_P$45") (pintype "bidirectional"))
      (node (ref "U$2") (pin "P$47") (pinfunction "+5V2_P$47") (pintype "bidirectional"))
      (node (ref "U11") (pin "6") (pinfunction "6_6") (pintype "passive"))
      (node (ref "U12") (pin "4") (pinfunction "FB_4") (pintype "input"))
      (node (ref "X1") (pin "1") (pinfunction "1_1") (pintype "passive"))
    )
    (net (code "122") (name "unconnected-(S1-PadB)") (class "Default")
      (node (ref "S1") (pin "B") (pinfunction "B_B") (pintype "passive"))
    )
    (net (code "123") (name "unconnected-(S1-PadB1)") (class "Default")
      (node (ref "S1") (pin "B1") (pinfunction "B1_B1") (pintype "passive"))
    )
    (net (code "124") (name "unconnected-(S1-S-Pad3)") (class "Default")
      (node (ref "S1") (pin "3") (pinfunction "S_3") (pintype "passive"))
    )
    (net (code "125") (name "unconnected-(U$1-NC1-PadP$5)") (class "Default")
      (node (ref "U$1") (pin "P$5") (pinfunction "NC1_P$5") (pintype "bidirectional"))
    )
    (net (code "126") (name "unconnected-(U$1-NC2-PadP$16)") (class "Default")
      (node (ref "U$1") (pin "P$16") (pinfunction "NC2_P$16") (pintype "bidirectional"))
    )
    (net (code "127") (name "unconnected-(U$2-NC1-PadP$5)") (class "Default")
      (node (ref "U$2") (pin "P$5") (pinfunction "NC1_P$5") (pintype "bidirectional"))
    )
    (net (code "128") (name "unconnected-(U$2-NC2-PadP$16)") (class "Default")
      (node (ref "U$2") (pin "P$16") (pinfunction "NC2_P$16") (pintype "bidirectional"))
    )
    (net (code "129") (name "unconnected-(U2A-B4-Pad8)") (class "Default")
      (node (ref "U2") (pin "8") (pinfunction "B4_8") (pintype "bidirectional"))
    )
    (net (code "130") (name "unconnected-(U6A-O3-Pad17)") (class "Default")
      (node (ref "U6") (pin "17") (pinfunction "O3_17") (pintype "bidirectional"))
    )
  )
)
